# 06_LMS7002M_Power.net
KiCad netlist of a schematic drawn in Altium Designer
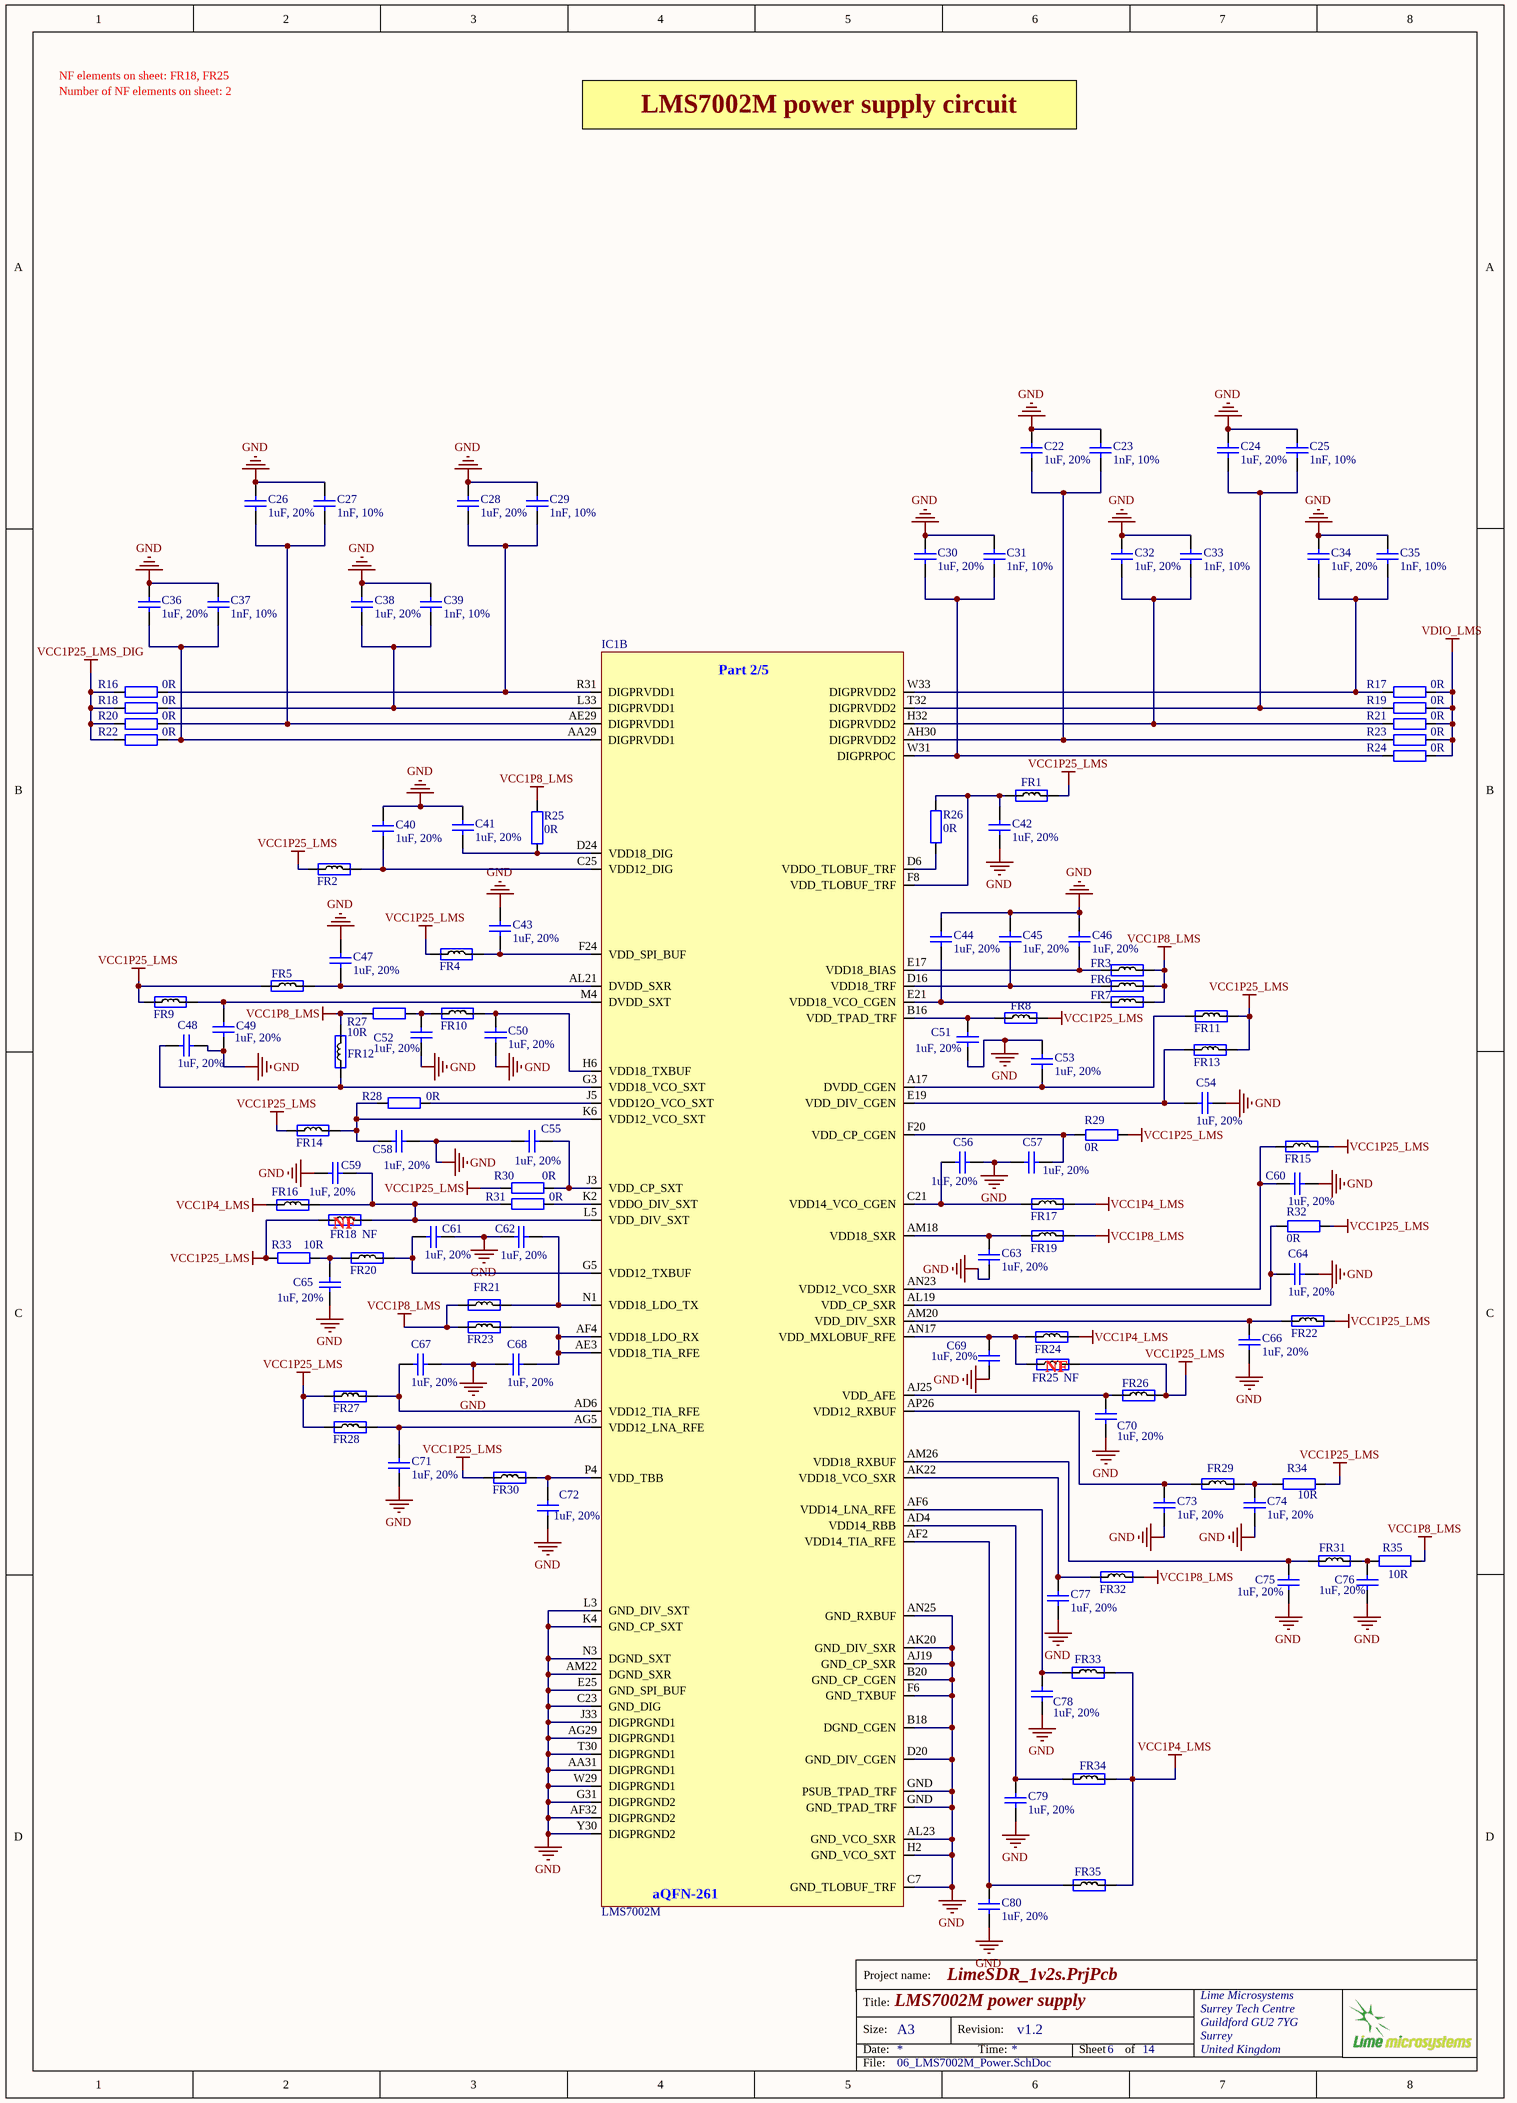
[diagram p0: 06_LMS7002M_Power.SchDoc]

(export (version "E")
  (design (tool "Eeschema 10.0.6"))
  (components
    (comp (ref "C22")
      (value "1uF, 20%")
      (footprint "CAP0201")
      (fields (field (name "TOLERANCE") "±20%") (field (name "MANUFACTURER") "TDK Corporation"))
      (libsource (lib "LimeMicroAltiumLib_schLib") (part "Cap_0402"))
    )
    (comp (ref "C23")
      (value "1nF, 10%")
      (footprint "CAP0201")
      (fields (field (name "TOLERANCE") "±10%") (field (name "MANUFACTURER") "TDK Corporation"))
      (libsource (lib "LimeMicroAltiumLib_schLib") (part "Cap_0402"))
    )
    (comp (ref "C24")
      (value "1uF, 20%")
      (footprint "CAP0201")
      (fields (field (name "TOLERANCE") "±20%") (field (name "MANUFACTURER") "TDK Corporation"))
      (libsource (lib "LimeMicroAltiumLib_schLib") (part "Cap_0402"))
    )
    (comp (ref "C25")
      (value "1nF, 10%")
      (footprint "CAP0201")
      (fields (field (name "TOLERANCE") "±10%") (field (name "MANUFACTURER") "TDK Corporation"))
      (libsource (lib "LimeMicroAltiumLib_schLib") (part "Cap_0402"))
    )
    (comp (ref "C26")
      (value "1uF, 20%")
      (footprint "CAP0201")
      (fields (field (name "TOLERANCE") "±20%") (field (name "MANUFACTURER") "TDK Corporation"))
      (libsource (lib "LimeMicroAltiumLib_schLib") (part "Cap_0402"))
    )
    (comp (ref "C27")
      (value "1nF, 10%")
      (footprint "CAP0201")
      (fields (field (name "TOLERANCE") "±10%") (field (name "MANUFACTURER") "TDK Corporation"))
      (libsource (lib "LimeMicroAltiumLib_schLib") (part "Cap_0402"))
    )
    (comp (ref "C28")
      (value "1uF, 20%")
      (footprint "CAP0201")
      (fields (field (name "TOLERANCE") "±20%") (field (name "MANUFACTURER") "TDK Corporation"))
      (libsource (lib "LimeMicroAltiumLib_schLib") (part "Cap_0402"))
    )
    (comp (ref "C29")
      (value "1nF, 10%")
      (footprint "CAP0201")
      (fields (field (name "TOLERANCE") "±10%") (field (name "MANUFACTURER") "TDK Corporation"))
      (libsource (lib "LimeMicroAltiumLib_schLib") (part "Cap_0402"))
    )
    (comp (ref "C30")
      (value "1uF, 20%")
      (footprint "CAP0201")
      (fields (field (name "TOLERANCE") "±20%") (field (name "MANUFACTURER") "TDK Corporation"))
      (libsource (lib "LimeMicroAltiumLib_schLib") (part "Cap_0402"))
    )
    (comp (ref "C31")
      (value "1nF, 10%")
      (footprint "CAP0201")
      (fields (field (name "TOLERANCE") "±10%") (field (name "MANUFACTURER") "TDK Corporation"))
      (libsource (lib "LimeMicroAltiumLib_schLib") (part "Cap_0402"))
    )
    (comp (ref "C32")
      (value "1uF, 20%")
      (footprint "CAP0201")
      (fields (field (name "TOLERANCE") "±20%") (field (name "MANUFACTURER") "TDK Corporation"))
      (libsource (lib "LimeMicroAltiumLib_schLib") (part "Cap_0402"))
    )
    (comp (ref "C33")
      (value "1nF, 10%")
      (footprint "CAP0201")
      (fields (field (name "TOLERANCE") "±10%") (field (name "MANUFACTURER") "TDK Corporation"))
      (libsource (lib "LimeMicroAltiumLib_schLib") (part "Cap_0402"))
    )
    (comp (ref "C34")
      (value "1uF, 20%")
      (footprint "CAP0201")
      (fields (field (name "TOLERANCE") "±20%") (field (name "MANUFACTURER") "TDK Corporation"))
      (libsource (lib "LimeMicroAltiumLib_schLib") (part "Cap_0402"))
    )
    (comp (ref "C35")
      (value "1nF, 10%")
      (footprint "CAP0201")
      (fields (field (name "TOLERANCE") "±10%") (field (name "MANUFACTURER") "TDK Corporation"))
      (libsource (lib "LimeMicroAltiumLib_schLib") (part "Cap_0402"))
    )
    (comp (ref "C36")
      (value "1uF, 20%")
      (footprint "CAP0201")
      (fields (field (name "TOLERANCE") "±20%") (field (name "MANUFACTURER") "TDK Corporation"))
      (libsource (lib "LimeMicroAltiumLib_schLib") (part "Cap_0402"))
    )
    (comp (ref "C37")
      (value "1nF, 10%")
      (footprint "CAP0201")
      (fields (field (name "TOLERANCE") "±10%") (field (name "MANUFACTURER") "TDK Corporation"))
      (libsource (lib "LimeMicroAltiumLib_schLib") (part "Cap_0402"))
    )
    (comp (ref "C38")
      (value "1uF, 20%")
      (footprint "CAP0201")
      (fields (field (name "TOLERANCE") "±20%") (field (name "MANUFACTURER") "TDK Corporation"))
      (libsource (lib "LimeMicroAltiumLib_schLib") (part "Cap_0402"))
    )
    (comp (ref "C39")
      (value "1nF, 10%")
      (footprint "CAP0201")
      (fields (field (name "TOLERANCE") "±10%") (field (name "MANUFACTURER") "TDK Corporation"))
      (libsource (lib "LimeMicroAltiumLib_schLib") (part "Cap_0402"))
    )
    (comp (ref "C40")
      (value "1uF, 20%")
      (footprint "CAP0201")
      (fields (field (name "TOLERANCE") "±20%") (field (name "MANUFACTURER") "TDK Corporation"))
      (libsource (lib "LimeMicroAltiumLib_schLib") (part "Cap_0402"))
    )
    (comp (ref "C41")
      (value "1uF, 20%")
      (footprint "CAP0201")
      (fields (field (name "TOLERANCE") "±20%") (field (name "MANUFACTURER") "TDK Corporation"))
      (libsource (lib "LimeMicroAltiumLib_schLib") (part "Cap_0402"))
    )
    (comp (ref "C42")
      (value "1uF, 20%")
      (footprint "CAP0201")
      (fields (field (name "TOLERANCE") "±20%") (field (name "MANUFACTURER") "TDK Corporation"))
      (libsource (lib "LimeMicroAltiumLib_schLib") (part "Cap_0402"))
    )
    (comp (ref "C43")
      (value "1uF, 20%")
      (footprint "CAP0201")
      (fields (field (name "TOLERANCE") "±20%") (field (name "MANUFACTURER") "TDK Corporation"))
      (libsource (lib "LimeMicroAltiumLib_schLib") (part "Cap_0402"))
    )
    (comp (ref "C44")
      (value "1uF, 20%")
      (footprint "CAP0201")
      (fields (field (name "TOLERANCE") "±20%") (field (name "MANUFACTURER") "TDK Corporation"))
      (libsource (lib "LimeMicroAltiumLib_schLib") (part "Cap_0402"))
    )
    (comp (ref "C45")
      (value "1uF, 20%")
      (footprint "CAP0201")
      (fields (field (name "TOLERANCE") "±20%") (field (name "MANUFACTURER") "TDK Corporation"))
      (libsource (lib "LimeMicroAltiumLib_schLib") (part "Cap_0402"))
    )
    (comp (ref "C46")
      (value "1uF, 20%")
      (footprint "CAP0201")
      (fields (field (name "TOLERANCE") "±20%") (field (name "MANUFACTURER") "TDK Corporation"))
      (libsource (lib "LimeMicroAltiumLib_schLib") (part "Cap_0402"))
    )
    (comp (ref "C47")
      (value "1uF, 20%")
      (footprint "CAP0201")
      (fields (field (name "TOLERANCE") "±20%") (field (name "MANUFACTURER") "TDK Corporation"))
      (libsource (lib "LimeMicroAltiumLib_schLib") (part "Cap_0402"))
    )
    (comp (ref "C48")
      (value "1uF, 20%")
      (footprint "CAP0201")
      (fields (field (name "TOLERANCE") "±20%") (field (name "MANUFACTURER") "TDK Corporation"))
      (libsource (lib "LimeMicroAltiumLib_schLib") (part "Cap_0402"))
    )
    (comp (ref "C49")
      (value "1uF, 20%")
      (footprint "CAP0201")
      (fields (field (name "TOLERANCE") "±20%") (field (name "MANUFACTURER") "TDK Corporation"))
      (libsource (lib "LimeMicroAltiumLib_schLib") (part "Cap_0402"))
    )
    (comp (ref "C50")
      (value "1uF, 20%")
      (footprint "CAP0201")
      (fields (field (name "TOLERANCE") "±20%") (field (name "MANUFACTURER") "TDK Corporation"))
      (libsource (lib "LimeMicroAltiumLib_schLib") (part "Cap_0402"))
    )
    (comp (ref "C51")
      (value "1uF, 20%")
      (footprint "CAP0201")
      (fields (field (name "TOLERANCE") "±20%") (field (name "MANUFACTURER") "TDK Corporation"))
      (libsource (lib "LimeMicroAltiumLib_schLib") (part "Cap_0402"))
    )
    (comp (ref "C52")
      (value "1uF, 20%")
      (footprint "CAP0201")
      (fields (field (name "TOLERANCE") "±20%") (field (name "MANUFACTURER") "TDK Corporation"))
      (libsource (lib "LimeMicroAltiumLib_schLib") (part "Cap_0402"))
    )
    (comp (ref "C53")
      (value "1uF, 20%")
      (footprint "CAP0201")
      (fields (field (name "TOLERANCE") "±20%") (field (name "MANUFACTURER") "TDK Corporation"))
      (libsource (lib "LimeMicroAltiumLib_schLib") (part "Cap_0402"))
    )
    (comp (ref "C54")
      (value "1uF, 20%")
      (footprint "CAP0201")
      (fields (field (name "TOLERANCE") "±20%") (field (name "MANUFACTURER") "TDK Corporation"))
      (libsource (lib "LimeMicroAltiumLib_schLib") (part "Cap_0402"))
    )
    (comp (ref "C55")
      (value "1uF, 20%")
      (footprint "CAP0201")
      (fields (field (name "TOLERANCE") "±20%") (field (name "MANUFACTURER") "TDK Corporation"))
      (libsource (lib "LimeMicroAltiumLib_schLib") (part "Cap_0402"))
    )
    (comp (ref "C56")
      (value "1uF, 20%")
      (footprint "CAP0201")
      (fields (field (name "TOLERANCE") "±20%") (field (name "MANUFACTURER") "TDK Corporation"))
      (libsource (lib "LimeMicroAltiumLib_schLib") (part "Cap_0402"))
    )
    (comp (ref "C57")
      (value "1uF, 20%")
      (footprint "CAP0201")
      (fields (field (name "TOLERANCE") "±20%") (field (name "MANUFACTURER") "TDK Corporation"))
      (libsource (lib "LimeMicroAltiumLib_schLib") (part "Cap_0402"))
    )
    (comp (ref "C58")
      (value "1uF, 20%")
      (footprint "CAP0201")
      (fields (field (name "TOLERANCE") "±20%") (field (name "MANUFACTURER") "TDK Corporation"))
      (libsource (lib "LimeMicroAltiumLib_schLib") (part "Cap_0402"))
    )
    (comp (ref "C59")
      (value "1uF, 20%")
      (footprint "CAP0201")
      (fields (field (name "TOLERANCE") "±20%") (field (name "MANUFACTURER") "TDK Corporation"))
      (libsource (lib "LimeMicroAltiumLib_schLib") (part "Cap_0402"))
    )
    (comp (ref "C60")
      (value "1uF, 20%")
      (footprint "CAP0201")
      (fields (field (name "TOLERANCE") "±20%") (field (name "MANUFACTURER") "TDK Corporation"))
      (libsource (lib "LimeMicroAltiumLib_schLib") (part "Cap_0402"))
    )
    (comp (ref "C61")
      (value "1uF, 20%")
      (footprint "CAP0201")
      (fields (field (name "TOLERANCE") "±20%") (field (name "MANUFACTURER") "TDK Corporation"))
      (libsource (lib "LimeMicroAltiumLib_schLib") (part "Cap_0402"))
    )
    (comp (ref "C62")
      (value "1uF, 20%")
      (footprint "CAP0201")
      (fields (field (name "TOLERANCE") "±20%") (field (name "MANUFACTURER") "TDK Corporation"))
      (libsource (lib "LimeMicroAltiumLib_schLib") (part "Cap_0402"))
    )
    (comp (ref "C63")
      (value "1uF, 20%")
      (footprint "CAP0201")
      (fields (field (name "TOLERANCE") "±20%") (field (name "MANUFACTURER") "TDK Corporation"))
      (libsource (lib "LimeMicroAltiumLib_schLib") (part "Cap_0402"))
    )
    (comp (ref "C64")
      (value "1uF, 20%")
      (footprint "CAP0201")
      (fields (field (name "TOLERANCE") "±20%") (field (name "MANUFACTURER") "TDK Corporation"))
      (libsource (lib "LimeMicroAltiumLib_schLib") (part "Cap_0402"))
    )
    (comp (ref "C65")
      (value "1uF, 20%")
      (footprint "CAP0201")
      (fields (field (name "TOLERANCE") "±20%") (field (name "MANUFACTURER") "TDK Corporation"))
      (libsource (lib "LimeMicroAltiumLib_schLib") (part "Cap_0402"))
    )
    (comp (ref "C66")
      (value "1uF, 20%")
      (footprint "CAP0201")
      (fields (field (name "TOLERANCE") "±20%") (field (name "MANUFACTURER") "TDK Corporation"))
      (libsource (lib "LimeMicroAltiumLib_schLib") (part "Cap_0402"))
    )
    (comp (ref "C67")
      (value "1uF, 20%")
      (footprint "CAP0201")
      (fields (field (name "TOLERANCE") "±20%") (field (name "MANUFACTURER") "TDK Corporation"))
      (libsource (lib "LimeMicroAltiumLib_schLib") (part "Cap_0402"))
    )
    (comp (ref "C68")
      (value "1uF, 20%")
      (footprint "CAP0201")
      (fields (field (name "TOLERANCE") "±20%") (field (name "MANUFACTURER") "TDK Corporation"))
      (libsource (lib "LimeMicroAltiumLib_schLib") (part "Cap_0402"))
    )
    (comp (ref "C69")
      (value "1uF, 20%")
      (footprint "CAP0201")
      (fields (field (name "TOLERANCE") "±20%") (field (name "MANUFACTURER") "TDK Corporation"))
      (libsource (lib "LimeMicroAltiumLib_schLib") (part "Cap_0402"))
    )
    (comp (ref "C70")
      (value "1uF, 20%")
      (footprint "CAP0201")
      (fields (field (name "TOLERANCE") "±20%") (field (name "MANUFACTURER") "TDK Corporation"))
      (libsource (lib "LimeMicroAltiumLib_schLib") (part "Cap_0402"))
    )
    (comp (ref "C71")
      (value "1uF, 20%")
      (footprint "CAP0201")
      (fields (field (name "TOLERANCE") "±20%") (field (name "MANUFACTURER") "TDK Corporation"))
      (libsource (lib "LimeMicroAltiumLib_schLib") (part "Cap_0402"))
    )
    (comp (ref "C72")
      (value "1uF, 20%")
      (footprint "CAP0201")
      (fields (field (name "TOLERANCE") "±20%") (field (name "MANUFACTURER") "TDK Corporation"))
      (libsource (lib "LimeMicroAltiumLib_schLib") (part "Cap_0402"))
    )
    (comp (ref "C73")
      (value "1uF, 20%")
      (footprint "CAP0201")
      (fields (field (name "TOLERANCE") "±20%") (field (name "MANUFACTURER") "TDK Corporation"))
      (libsource (lib "LimeMicroAltiumLib_schLib") (part "Cap_0402"))
    )
    (comp (ref "C74")
      (value "1uF, 20%")
      (footprint "CAP0201")
      (fields (field (name "TOLERANCE") "±20%") (field (name "MANUFACTURER") "TDK Corporation"))
      (libsource (lib "LimeMicroAltiumLib_schLib") (part "Cap_0402"))
    )
    (comp (ref "C75")
      (value "1uF, 20%")
      (footprint "CAP0201")
      (fields (field (name "TOLERANCE") "±20%") (field (name "MANUFACTURER") "TDK Corporation"))
      (libsource (lib "LimeMicroAltiumLib_schLib") (part "Cap_0402"))
    )
    (comp (ref "C76")
      (value "1uF, 20%")
      (footprint "CAP0201")
      (fields (field (name "TOLERANCE") "±20%") (field (name "MANUFACTURER") "TDK Corporation"))
      (libsource (lib "LimeMicroAltiumLib_schLib") (part "Cap_0402"))
    )
    (comp (ref "C77")
      (value "1uF, 20%")
      (footprint "CAP0201")
      (fields (field (name "TOLERANCE") "±20%") (field (name "MANUFACTURER") "TDK Corporation"))
      (libsource (lib "LimeMicroAltiumLib_schLib") (part "Cap_0402"))
    )
    (comp (ref "C78")
      (value "1uF, 20%")
      (footprint "CAP0201")
      (fields (field (name "TOLERANCE") "±20%") (field (name "MANUFACTURER") "TDK Corporation"))
      (libsource (lib "LimeMicroAltiumLib_schLib") (part "Cap_0402"))
    )
    (comp (ref "C79")
      (value "1uF, 20%")
      (footprint "CAP0201")
      (fields (field (name "TOLERANCE") "±20%") (field (name "MANUFACTURER") "TDK Corporation"))
      (libsource (lib "LimeMicroAltiumLib_schLib") (part "Cap_0402"))
    )
    (comp (ref "C80")
      (value "1uF, 20%")
      (footprint "CAP0201")
      (fields (field (name "TOLERANCE") "±20%") (field (name "MANUFACTURER") "TDK Corporation"))
      (libsource (lib "LimeMicroAltiumLib_schLib") (part "Cap_0402"))
    )
    (comp (ref "FR1")
      (value "Ferrite")
      (footprint "RES0201")
      (fields (field (name "MANUFACTURER") "Taiyo Yuden"))
      (libsource (lib "LimeMicroAltiumLib_schLib") (part "Ferrite"))
    )
    (comp (ref "FR2")
      (value "Ferrite")
      (footprint "RES0201")
      (fields (field (name "MANUFACTURER") "Taiyo Yuden"))
      (libsource (lib "LimeMicroAltiumLib_schLib") (part "Ferrite"))
    )
    (comp (ref "FR3")
      (value "Ferrite")
      (footprint "RES0201")
      (fields (field (name "MANUFACTURER") "Taiyo Yuden"))
      (libsource (lib "LimeMicroAltiumLib_schLib") (part "Ferrite"))
    )
    (comp (ref "FR4")
      (value "Ferrite")
      (footprint "RES0201")
      (fields (field (name "MANUFACTURER") "Taiyo Yuden"))
      (libsource (lib "LimeMicroAltiumLib_schLib") (part "Ferrite"))
    )
    (comp (ref "FR5")
      (value "Ferrite")
      (footprint "RES0201")
      (fields (field (name "MANUFACTURER") "Taiyo Yuden"))
      (libsource (lib "LimeMicroAltiumLib_schLib") (part "Ferrite"))
    )
    (comp (ref "FR6")
      (value "Ferrite")
      (footprint "RES0201")
      (fields (field (name "MANUFACTURER") "Taiyo Yuden"))
      (libsource (lib "LimeMicroAltiumLib_schLib") (part "Ferrite"))
    )
    (comp (ref "FR7")
      (value "Ferrite")
      (footprint "RES0201")
      (fields (field (name "MANUFACTURER") "Taiyo Yuden"))
      (libsource (lib "LimeMicroAltiumLib_schLib") (part "Ferrite"))
    )
    (comp (ref "FR8")
      (value "Ferrite")
      (footprint "RES0201")
      (fields (field (name "MANUFACTURER") "Taiyo Yuden"))
      (libsource (lib "LimeMicroAltiumLib_schLib") (part "Ferrite"))
    )
    (comp (ref "FR9")
      (value "Ferrite")
      (footprint "RES0201")
      (fields (field (name "MANUFACTURER") "Taiyo Yuden"))
      (libsource (lib "LimeMicroAltiumLib_schLib") (part "Ferrite"))
    )
    (comp (ref "FR10")
      (value "Ferrite")
      (footprint "RES0201")
      (fields (field (name "MANUFACTURER") "Taiyo Yuden"))
      (libsource (lib "LimeMicroAltiumLib_schLib") (part "Ferrite"))
    )
    (comp (ref "FR11")
      (value "Ferrite")
      (footprint "RES0201")
      (fields (field (name "MANUFACTURER") "Taiyo Yuden"))
      (libsource (lib "LimeMicroAltiumLib_schLib") (part "Ferrite"))
    )
    (comp (ref "FR12")
      (value "Ferrite")
      (footprint "RES0201")
      (fields (field (name "MANUFACTURER") "Taiyo Yuden"))
      (libsource (lib "LimeMicroAltiumLib_schLib") (part "Ferrite"))
    )
    (comp (ref "FR13")
      (value "Ferrite")
      (footprint "RES0201")
      (fields (field (name "MANUFACTURER") "Taiyo Yuden"))
      (libsource (lib "LimeMicroAltiumLib_schLib") (part "Ferrite"))
    )
    (comp (ref "FR14")
      (value "Ferrite")
      (footprint "RES0201")
      (fields (field (name "MANUFACTURER") "Taiyo Yuden"))
      (libsource (lib "LimeMicroAltiumLib_schLib") (part "Ferrite"))
    )
    (comp (ref "FR15")
      (value "Ferrite")
      (footprint "RES0201")
      (fields (field (name "MANUFACTURER") "Taiyo Yuden"))
      (libsource (lib "LimeMicroAltiumLib_schLib") (part "Ferrite"))
    )
    (comp (ref "FR16")
      (value "Ferrite")
      (footprint "RES0201")
      (fields (field (name "MANUFACTURER") "Taiyo Yuden"))
      (libsource (lib "LimeMicroAltiumLib_schLib") (part "Ferrite"))
    )
    (comp (ref "FR17")
      (value "Ferrite")
      (footprint "RES0201")
      (fields (field (name "MANUFACTURER") "Taiyo Yuden"))
      (libsource (lib "LimeMicroAltiumLib_schLib") (part "Ferrite"))
    )
    (comp (ref "FR18")
      (value "Ferrite")
      (footprint "RES0201")
      (fields (field (name "MANUFACTURER") "Taiyo Yuden") (field (name "ASSEMBLY INFO") "NF"))
      (libsource (lib "LimeMicroAltiumLib_schLib") (part "Ferrite"))
    )
    (comp (ref "FR19")
      (value "Ferrite")
      (footprint "RES0201")
      (fields (field (name "MANUFACTURER") "Taiyo Yuden"))
      (libsource (lib "LimeMicroAltiumLib_schLib") (part "Ferrite"))
    )
    (comp (ref "FR20")
      (value "Ferrite")
      (footprint "RES0201")
      (fields (field (name "MANUFACTURER") "Taiyo Yuden"))
      (libsource (lib "LimeMicroAltiumLib_schLib") (part "Ferrite"))
    )
    (comp (ref "FR21")
      (value "Ferrite")
      (footprint "RES0201")
      (fields (field (name "MANUFACTURER") "Taiyo Yuden"))
      (libsource (lib "LimeMicroAltiumLib_schLib") (part "Ferrite"))
    )
    (comp (ref "FR22")
      (value "Ferrite")
      (footprint "RES0201")
      (fields (field (name "MANUFACTURER") "Taiyo Yuden"))
      (libsource (lib "LimeMicroAltiumLib_schLib") (part "Ferrite"))
    )
    (comp (ref "FR23")
      (value "Ferrite")
      (footprint "RES0201")
      (fields (field (name "MANUFACTURER") "Taiyo Yuden"))
      (libsource (lib "LimeMicroAltiumLib_schLib") (part "Ferrite"))
    )
    (comp (ref "FR24")
      (value "Ferrite")
      (footprint "RES0201")
      (fields (field (name "MANUFACTURER") "Taiyo Yuden"))
      (libsource (lib "LimeMicroAltiumLib_schLib") (part "Ferrite"))
    )
    (comp (ref "FR25")
      (value "Ferrite")
      (footprint "RES0201")
      (fields (field (name "MANUFACTURER") "Taiyo Yuden") (field (name "ASSEMBLY INFO") "NF"))
      (libsource (lib "LimeMicroAltiumLib_schLib") (part "Ferrite"))
    )
    (comp (ref "FR26")
      (value "Ferrite")
      (footprint "RES0201")
      (fields (field (name "MANUFACTURER") "Taiyo Yuden"))
      (libsource (lib "LimeMicroAltiumLib_schLib") (part "Ferrite"))
    )
    (comp (ref "FR27")
      (value "Ferrite")
      (footprint "RES0201")
      (fields (field (name "MANUFACTURER") "Taiyo Yuden"))
      (libsource (lib "LimeMicroAltiumLib_schLib") (part "Ferrite"))
    )
    (comp (ref "FR28")
      (value "Ferrite")
      (footprint "RES0201")
      (fields (field (name "MANUFACTURER") "Taiyo Yuden"))
      (libsource (lib "LimeMicroAltiumLib_schLib") (part "Ferrite"))
    )
    (comp (ref "FR29")
      (value "Ferrite")
      (footprint "RES0201")
      (fields (field (name "MANUFACTURER") "Taiyo Yuden"))
      (libsource (lib "LimeMicroAltiumLib_schLib") (part "Ferrite"))
    )
    (comp (ref "FR30")
      (value "Ferrite")
      (footprint "RES0201")
      (fields (field (name "MANUFACTURER") "Taiyo Yuden"))
      (libsource (lib "LimeMicroAltiumLib_schLib") (part "Ferrite"))
    )
    (comp (ref "FR31")
      (value "Ferrite")
      (footprint "RES0201")
      (fields (field (name "MANUFACTURER") "Taiyo Yuden"))
      (libsource (lib "LimeMicroAltiumLib_schLib") (part "Ferrite"))
    )
    (comp (ref "FR32")
      (value "Ferrite")
      (footprint "RES0201")
      (fields (field (name "MANUFACTURER") "Taiyo Yuden"))
      (libsource (lib "LimeMicroAltiumLib_schLib") (part "Ferrite"))
    )
    (comp (ref "FR33")
      (value "Ferrite")
      (footprint "RES0201")
      (fields (field (name "MANUFACTURER") "Taiyo Yuden"))
      (libsource (lib "LimeMicroAltiumLib_schLib") (part "Ferrite"))
    )
    (comp (ref "FR34")
      (value "Ferrite")
      (footprint "RES0201")
      (fields (field (name "MANUFACTURER") "Taiyo Yuden"))
      (libsource (lib "LimeMicroAltiumLib_schLib") (part "Ferrite"))
    )
    (comp (ref "FR35")
      (value "Ferrite")
      (footprint "RES0201")
      (fields (field (name "MANUFACTURER") "Taiyo Yuden"))
      (libsource (lib "LimeMicroAltiumLib_schLib") (part "Ferrite"))
    )
    (comp (ref "IC1")
      (value "LMS7002M")
      (footprint "LMS7002M")
      (fields (field (name "MANUFACTURER") "Lime Microsystems"))
      (libsource (lib "LimeMicroAltiumLib_schLib") (part "LMS7002M"))
    )
    (comp (ref "R16")
      (value "0R")
      (footprint "RES0402")
      (fields (field (name "MANUFACTURER") "Yageo") (field (name "TOLERANCE") "Jumper"))
      (libsource (lib "LimeMicroAltiumLib_schLib") (part "Res_0402"))
    )
    (comp (ref "R17")
      (value "0R")
      (footprint "RES0402")
      (fields (field (name "MANUFACTURER") "Yageo") (field (name "TOLERANCE") "Jumper"))
      (libsource (lib "LimeMicroAltiumLib_schLib") (part "Res_0402"))
    )
    (comp (ref "R18")
      (value "0R")
      (footprint "RES0402")
      (fields (field (name "MANUFACTURER") "Yageo") (field (name "TOLERANCE") "Jumper"))
      (libsource (lib "LimeMicroAltiumLib_schLib") (part "Res_0402"))
    )
    (comp (ref "R19")
      (value "0R")
      (footprint "RES0402")
      (fields (field (name "MANUFACTURER") "Yageo") (field (name "TOLERANCE") "Jumper"))
      (libsource (lib "LimeMicroAltiumLib_schLib") (part "Res_0402"))
    )
    (comp (ref "R20")
      (value "0R")
      (footprint "RES0402")
      (fields (field (name "MANUFACTURER") "Yageo") (field (name "TOLERANCE") "Jumper"))
      (libsource (lib "LimeMicroAltiumLib_schLib") (part "Res_0402"))
    )
    (comp (ref "R21")
      (value "0R")
      (footprint "RES0402")
      (fields (field (name "MANUFACTURER") "Yageo") (field (name "TOLERANCE") "Jumper"))
      (libsource (lib "LimeMicroAltiumLib_schLib") (part "Res_0402"))
    )
    (comp (ref "R22")
      (value "0R")
      (footprint "RES0402")
      (fields (field (name "MANUFACTURER") "Yageo") (field (name "TOLERANCE") "Jumper"))
      (libsource (lib "LimeMicroAltiumLib_schLib") (part "Res_0402"))
    )
    (comp (ref "R23")
      (value "0R")
      (footprint "RES0402")
      (fields (field (name "MANUFACTURER") "Yageo") (field (name "TOLERANCE") "Jumper"))
      (libsource (lib "LimeMicroAltiumLib_schLib") (part "Res_0402"))
    )
    (comp (ref "R24")
      (value "0R")
      (footprint "RES0402")
      (fields (field (name "MANUFACTURER") "Yageo") (field (name "TOLERANCE") "Jumper"))
      (libsource (lib "LimeMicroAltiumLib_schLib") (part "Res_0402"))
    )
    (comp (ref "R25")
      (value "0R")
      (footprint "RES0201")
      (fields (field (name "MANUFACTURER") "Rohm Semiconductor") (field (name "TOLERANCE") "Jumper"))
      (libsource (lib "LimeMicroAltiumLib_schLib") (part "Res_0402"))
    )
    (comp (ref "R26")
      (value "0R")
      (footprint "RES0201")
      (fields (field (name "MANUFACTURER") "Rohm Semiconductor") (field (name "TOLERANCE") "Jumper"))
      (libsource (lib "LimeMicroAltiumLib_schLib") (part "Res_0402"))
    )
    (comp (ref "R27")
      (value "10R")
      (footprint "RES0201")
      (fields
        (field (name "MANUFACTURER") "Panasonic Electronic Components")
        (field (name "TOLERANCE") "±1%")
        (field (name "MANUFACTURER PART NUMBER") "ERJ-1GEF10R0C")
      )
      (libsource (lib "LimeMicroAltiumLib_schLib") (part "Res_0402"))
    )
    (comp (ref "R28")
      (value "0R")
      (footprint "RES0201")
      (fields (field (name "MANUFACTURER") "Rohm Semiconductor") (field (name "TOLERANCE") "Jumper"))
      (libsource (lib "LimeMicroAltiumLib_schLib") (part "Res_0402"))
    )
    (comp (ref "R29")
      (value "0R")
      (footprint "RES0201")
      (fields (field (name "MANUFACTURER") "Rohm Semiconductor") (field (name "TOLERANCE") "Jumper"))
      (libsource (lib "LimeMicroAltiumLib_schLib") (part "Res_0402"))
    )
    (comp (ref "R30")
      (value "0R")
      (footprint "RES0201")
      (fields (field (name "MANUFACTURER") "Rohm Semiconductor") (field (name "TOLERANCE") "Jumper"))
      (libsource (lib "LimeMicroAltiumLib_schLib") (part "Res_0402"))
    )
    (comp (ref "R31")
      (value "0R")
      (footprint "RES0201")
      (fields (field (name "MANUFACTURER") "Rohm Semiconductor") (field (name "TOLERANCE") "Jumper"))
      (libsource (lib "LimeMicroAltiumLib_schLib") (part "Res_0402"))
    )
    (comp (ref "R32")
      (value "0R")
      (footprint "RES0201")
      (fields (field (name "MANUFACTURER") "Rohm Semiconductor") (field (name "TOLERANCE") "Jumper"))
      (libsource (lib "LimeMicroAltiumLib_schLib") (part "Res_0402"))
    )
    (comp (ref "R33")
      (value "10R")
      (footprint "RES0201")
      (fields
        (field (name "MANUFACTURER") "Panasonic Electronic Components")
        (field (name "TOLERANCE") "±1%")
        (field (name "MANUFACTURER PART NUMBER") "ERJ-1GEF10R0C")
      )
      (libsource (lib "LimeMicroAltiumLib_schLib") (part "Res_0402"))
    )
    (comp (ref "R34")
      (value "10R")
      (footprint "RES0201")
      (fields
        (field (name "MANUFACTURER") "Panasonic Electronic Components")
        (field (name "TOLERANCE") "±1%")
        (field (name "MANUFACTURER PART NUMBER") "ERJ-1GEF10R0C")
      )
      (libsource (lib "LimeMicroAltiumLib_schLib") (part "Res_0402"))
    )
    (comp (ref "R35")
      (value "10R")
      (footprint "RES0201")
      (fields
        (field (name "MANUFACTURER") "Panasonic Electronic Components")
        (field (name "TOLERANCE") "±1%")
        (field (name "MANUFACTURER PART NUMBER") "ERJ-1GEF10R0C")
      )
      (libsource (lib "LimeMicroAltiumLib_schLib") (part "Res_0402"))
    )
  )
  (nets
    (net (code "1") (name "GND") (class "Default")
      (node (ref "C22") (pin "2") (pinfunction "2_2") (pintype "passive"))
      (node (ref "C23") (pin "2") (pinfunction "2_2") (pintype "passive"))
      (node (ref "C24") (pin "2") (pinfunction "2_2") (pintype "passive"))
      (node (ref "C25") (pin "2") (pinfunction "2_2") (pintype "passive"))
      (node (ref "C26") (pin "2") (pinfunction "2_2") (pintype "passive"))
      (node (ref "C27") (pin "2") (pinfunction "2_2") (pintype "passive"))
      (node (ref "C28") (pin "2") (pinfunction "2_2") (pintype "passive"))
      (node (ref "C29") (pin "2") (pinfunction "2_2") (pintype "passive"))
      (node (ref "C30") (pin "2") (pinfunction "2_2") (pintype "passive"))
      (node (ref "C31") (pin "2") (pinfunction "2_2") (pintype "passive"))
      (node (ref "C32") (pin "2") (pinfunction "2_2") (pintype "passive"))
      (node (ref "C33") (pin "2") (pinfunction "2_2") (pintype "passive"))
      (node (ref "C34") (pin "2") (pinfunction "2_2") (pintype "passive"))
      (node (ref "C35") (pin "2") (pinfunction "2_2") (pintype "passive"))
      (node (ref "C36") (pin "2") (pinfunction "2_2") (pintype "passive"))
      (node (ref "C37") (pin "2") (pinfunction "2_2") (pintype "passive"))
      (node (ref "C38") (pin "2") (pinfunction "2_2") (pintype "passive"))
      (node (ref "C39") (pin "2") (pinfunction "2_2") (pintype "passive"))
      (node (ref "C40") (pin "2") (pinfunction "2_2") (pintype "passive"))
      (node (ref "C41") (pin "2") (pinfunction "2_2") (pintype "passive"))
      (node (ref "C42") (pin "2") (pinfunction "2_2") (pintype "passive"))
      (node (ref "C43") (pin "2") (pinfunction "2_2") (pintype "passive"))
      (node (ref "C44") (pin "2") (pinfunction "2_2") (pintype "passive"))
      (node (ref "C45") (pin "2") (pinfunction "2_2") (pintype "passive"))
      (node (ref "C46") (pin "2") (pinfunction "2_2") (pintype "passive"))
      (node (ref "C47") (pin "2") (pinfunction "2_2") (pintype "passive"))
      (node (ref "C48") (pin "2") (pinfunction "2_2") (pintype "passive"))
      (node (ref "C49") (pin "2") (pinfunction "2_2") (pintype "passive"))
      (node (ref "C50") (pin "2") (pinfunction "2_2") (pintype "passive"))
      (node (ref "C51") (pin "2") (pinfunction "2_2") (pintype "passive"))
      (node (ref "C52") (pin "2") (pinfunction "2_2") (pintype "passive"))
      (node (ref "C53") (pin "2") (pinfunction "2_2") (pintype "passive"))
      (node (ref "C54") (pin "2") (pinfunction "2_2") (pintype "passive"))
      (node (ref "C55") (pin "2") (pinfunction "2_2") (pintype "passive"))
      (node (ref "C56") (pin "2") (pinfunction "2_2") (pintype "passive"))
      (node (ref "C57") (pin "2") (pinfunction "2_2") (pintype "passive"))
      (node (ref "C58") (pin "1") (pinfunction "1_1") (pintype "passive"))
      (node (ref "C59") (pin "2") (pinfunction "2_2") (pintype "passive"))
      (node (ref "C60") (pin "2") (pinfunction "2_2") (pintype "passive"))
      (node (ref "C61") (pin "2") (pinfunction "2_2") (pintype "passive"))
      (node (ref "C62") (pin "2") (pinfunction "2_2") (pintype "passive"))
      (node (ref "C63") (pin "2") (pinfunction "2_2") (pintype "passive"))
      (node (ref "C64") (pin "2") (pinfunction "2_2") (pintype "passive"))
      (node (ref "C65") (pin "2") (pinfunction "2_2") (pintype "passive"))
      (node (ref "C66") (pin "2") (pinfunction "2_2") (pintype "passive"))
      (node (ref "C67") (pin "2") (pinfunction "2_2") (pintype "passive"))
      (node (ref "C68") (pin "2") (pinfunction "2_2") (pintype "passive"))
      (node (ref "C69") (pin "2") (pinfunction "2_2") (pintype "passive"))
      (node (ref "C70") (pin "2") (pinfunction "2_2") (pintype "passive"))
      (node (ref "C71") (pin "2") (pinfunction "2_2") (pintype "passive"))
      (node (ref "C72") (pin "2") (pinfunction "2_2") (pintype "passive"))
      (node (ref "C73") (pin "2") (pinfunction "2_2") (pintype "passive"))
      (node (ref "C74") (pin "2") (pinfunction "2_2") (pintype "passive"))
      (node (ref "C75") (pin "2") (pinfunction "2_2") (pintype "passive"))
      (node (ref "C76") (pin "2") (pinfunction "2_2") (pintype "passive"))
      (node (ref "C77") (pin "2") (pinfunction "2_2") (pintype "passive"))
      (node (ref "C78") (pin "2") (pinfunction "2_2") (pintype "passive"))
      (node (ref "C79") (pin "2") (pinfunction "2_2") (pintype "passive"))
      (node (ref "C80") (pin "2") (pinfunction "2_2") (pintype "passive"))
      (node (ref "IC1") (pin "AA31") (pinfunction "DIGPRGND1_AA31") (pintype "passive"))
      (node (ref "IC1") (pin "AF32") (pinfunction "DIGPRGND2_AF32") (pintype "passive"))
      (node (ref "IC1") (pin "AG29") (pinfunction "DIGPRGND1_AG29") (pintype "passive"))
      (node (ref "IC1") (pin "AJ19") (pinfunction "GND_CP_SXR_AJ19") (pintype "passive"))
      (node (ref "IC1") (pin "AK20") (pinfunction "GND_DIV_SXR_AK20") (pintype "passive"))
      (node (ref "IC1") (pin "AL23") (pinfunction "GND_VCO_SXR_AL23") (pintype "passive"))
      (node (ref "IC1") (pin "AM22") (pinfunction "DGND_SXR_AM22") (pintype "passive"))
      (node (ref "IC1") (pin "AN25") (pinfunction "GND_RXBUF_AN25") (pintype "passive"))
      (node (ref "IC1") (pin "B18") (pinfunction "DGND_CGEN_B18") (pintype "passive"))
      (node (ref "IC1") (pin "B20") (pinfunction "GND_CP_CGEN_B20") (pintype "passive"))
      (node (ref "IC1") (pin "C23") (pinfunction "GND_DIG_C23") (pintype "passive"))
      (node (ref "IC1") (pin "C7") (pinfunction "GND_TLOBUF_TRF_C7") (pintype "passive"))
      (node (ref "IC1") (pin "D20") (pinfunction "GND_DIV_CGEN_D20") (pintype "passive"))
      (node (ref "IC1") (pin "E25") (pinfunction "GND_SPI_BUF_E25") (pintype "passive"))
      (node (ref "IC1") (pin "F6") (pinfunction "GND_TXBUF_F6") (pintype "passive"))
      (node (ref "IC1") (pin "G31") (pinfunction "DIGPRGND2_G31") (pintype "passive"))
      (node (ref "IC1") (pin "GND") (pinfunction "GND_TPAD_TRF_GND") (pintype "passive"))
      (node (ref "IC1") (pin "H2") (pinfunction "GND_VCO_SXT_H2") (pintype "passive"))
      (node (ref "IC1") (pin "J33") (pinfunction "DIGPRGND1_J33") (pintype "passive"))
      (node (ref "IC1") (pin "K4") (pinfunction "GND_CP_SXT_K4") (pintype "passive"))
      (node (ref "IC1") (pin "L3") (pinfunction "GND_DIV_SXT_L3") (pintype "passive"))
      (node (ref "IC1") (pin "N3") (pinfunction "DGND_SXT_N3") (pintype "passive"))
      (node (ref "IC1") (pin "T30") (pinfunction "DIGPRGND1_T30") (pintype "passive"))
      (node (ref "IC1") (pin "W29") (pinfunction "DIGPRGND1_W29") (pintype "passive"))
      (node (ref "IC1") (pin "Y30") (pinfunction "DIGPRGND2_Y30") (pintype "passive"))
    )
    (net (code "2") (name "Net-(C22-Pad1)") (class "Default")
      (node (ref "C22") (pin "1") (pinfunction "1_1") (pintype "passive"))
      (node (ref "C23") (pin "1") (pinfunction "1_1") (pintype "passive"))
      (node (ref "IC1") (pin "AH30") (pinfunction "DIGPRVDD2_AH30") (pintype "passive"))
      (node (ref "R23") (pin "2") (pinfunction "2_2") (pintype "passive"))
    )
    (net (code "3") (name "Net-(C24-Pad1)") (class "Default")
      (node (ref "C24") (pin "1") (pinfunction "1_1") (pintype "passive"))
      (node (ref "C25") (pin "1") (pinfunction "1_1") (pintype "passive"))
      (node (ref "IC1") (pin "T32") (pinfunction "DIGPRVDD2_T32") (pintype "passive"))
      (node (ref "R19") (pin "2") (pinfunction "2_2") (pintype "passive"))
    )
    (net (code "4") (name "Net-(C26-Pad1)") (class "Default")
      (node (ref "C26") (pin "1") (pinfunction "1_1") (pintype "passive"))
      (node (ref "C27") (pin "1") (pinfunction "1_1") (pintype "passive"))
      (node (ref "IC1") (pin "AE29") (pinfunction "DIGPRVDD1_AE29") (pintype "passive"))
      (node (ref "R20") (pin "1") (pinfunction "1_1") (pintype "passive"))
    )
    (net (code "5") (name "Net-(C28-Pad1)") (class "Default")
      (node (ref "C28") (pin "1") (pinfunction "1_1") (pintype "passive"))
      (node (ref "C29") (pin "1") (pinfunction "1_1") (pintype "passive"))
      (node (ref "IC1") (pin "R31") (pinfunction "DIGPRVDD1_R31") (pintype "passive"))
      (node (ref "R16") (pin "1") (pinfunction "1_1") (pintype "passive"))
    )
    (net (code "6") (name "Net-(C32-Pad1)") (class "Default")
      (node (ref "C32") (pin "1") (pinfunction "1_1") (pintype "passive"))
      (node (ref "C33") (pin "1") (pinfunction "1_1") (pintype "passive"))
      (node (ref "IC1") (pin "H32") (pinfunction "DIGPRVDD2_H32") (pintype "passive"))
      (node (ref "R21") (pin "2") (pinfunction "2_2") (pintype "passive"))
    )
    (net (code "7") (name "Net-(C34-Pad1)") (class "Default")
      (node (ref "C34") (pin "1") (pinfunction "1_1") (pintype "passive"))
      (node (ref "C35") (pin "1") (pinfunction "1_1") (pintype "passive"))
      (node (ref "IC1") (pin "W33") (pinfunction "DIGPRVDD2_W33") (pintype "passive"))
      (node (ref "R17") (pin "2") (pinfunction "2_2") (pintype "passive"))
    )
    (net (code "8") (name "Net-(C36-Pad1)") (class "Default")
      (node (ref "C36") (pin "1") (pinfunction "1_1") (pintype "passive"))
      (node (ref "C37") (pin "1") (pinfunction "1_1") (pintype "passive"))
      (node (ref "IC1") (pin "AA29") (pinfunction "DIGPRVDD1_AA29") (pintype "passive"))
      (node (ref "R22") (pin "1") (pinfunction "1_1") (pintype "passive"))
    )
    (net (code "9") (name "Net-(C38-Pad1)") (class "Default")
      (node (ref "C38") (pin "1") (pinfunction "1_1") (pintype "passive"))
      (node (ref "C39") (pin "1") (pinfunction "1_1") (pintype "passive"))
      (node (ref "IC1") (pin "L33") (pinfunction "DIGPRVDD1_L33") (pintype "passive"))
      (node (ref "R18") (pin "1") (pinfunction "1_1") (pintype "passive"))
    )
    (net (code "10") (name "Net-(C52-Pad1)") (class "Default")
      (node (ref "C52") (pin "1") (pinfunction "1_1") (pintype "passive"))
      (node (ref "FR10") (pin "1") (pinfunction "1_1") (pintype "passive"))
      (node (ref "R27") (pin "1") (pinfunction "1_1") (pintype "passive"))
    )
    (net (code "11") (name "Net-(C65-Pad1)") (class "Default")
      (node (ref "C65") (pin "1") (pinfunction "1_1") (pintype "passive"))
      (node (ref "FR20") (pin "1") (pinfunction "1_1") (pintype "passive"))
      (node (ref "R33") (pin "1") (pinfunction "1_1") (pintype "passive"))
    )
    (net (code "12") (name "Net-(C74-Pad1)") (class "Default")
      (node (ref "C74") (pin "1") (pinfunction "1_1") (pintype "passive"))
      (node (ref "FR29") (pin "2") (pinfunction "2_2") (pintype "passive"))
      (node (ref "R34") (pin "2") (pinfunction "2_2") (pintype "passive"))
    )
    (net (code "13") (name "Net-(C76-Pad1)") (class "Default")
      (node (ref "C76") (pin "1") (pinfunction "1_1") (pintype "passive"))
      (node (ref "FR31") (pin "2") (pinfunction "2_2") (pintype "passive"))
      (node (ref "R35") (pin "2") (pinfunction "2_2") (pintype "passive"))
    )
    (net (code "14") (name "Net-(IC1B-DIGPRPOC)") (class "Default")
      (node (ref "C30") (pin "1") (pinfunction "1_1") (pintype "passive"))
      (node (ref "C31") (pin "1") (pinfunction "1_1") (pintype "passive"))
      (node (ref "IC1") (pin "W31") (pinfunction "DIGPRPOC_W31") (pintype "passive"))
      (node (ref "R24") (pin "2") (pinfunction "2_2") (pintype "passive"))
    )
    (net (code "15") (name "Net-(IC1B-DVDD_CGEN)") (class "Default")
      (node (ref "C53") (pin "1") (pinfunction "1_1") (pintype "passive"))
      (node (ref "FR11") (pin "1") (pinfunction "1_1") (pintype "passive"))
      (node (ref "IC1") (pin "A17") (pinfunction "DVDD_CGEN_A17") (pintype "passive"))
    )
    (net (code "16") (name "Net-(IC1B-DVDD_SXR)") (class "Default")
      (node (ref "C47") (pin "1") (pinfunction "1_1") (pintype "passive"))
      (node (ref "FR5") (pin "2") (pinfunction "2_2") (pintype "passive"))
      (node (ref "IC1") (pin "AL21") (pinfunction "DVDD_SXR_AL21") (pintype "passive"))
    )
    (net (code "17") (name "Net-(IC1B-DVDD_SXT)") (class "Default")
      (node (ref "C49") (pin "1") (pinfunction "1_1") (pintype "passive"))
      (node (ref "FR9") (pin "2") (pinfunction "2_2") (pintype "passive"))
      (node (ref "IC1") (pin "M4") (pinfunction "DVDD_SXT_M4") (pintype "passive"))
    )
    (net (code "18") (name "Net-(IC1B-VDD12O_VCO_SXT)") (class "Default")
      (node (ref "IC1") (pin "J5") (pinfunction "VDD12O_VCO_SXT_J5") (pintype "passive"))
      (node (ref "R28") (pin "1") (pinfunction "1_1") (pintype "passive"))
    )
    (net (code "19") (name "Net-(IC1B-VDD12_DIG)") (class "Default")
      (node (ref "C40") (pin "1") (pinfunction "1_1") (pintype "passive"))
      (node (ref "FR2") (pin "2") (pinfunction "2_2") (pintype "passive"))
      (node (ref "IC1") (pin "C25") (pinfunction "VDD12_DIG_C25") (pintype "passive"))
    )
    (net (code "20") (name "Net-(IC1B-VDD12_LNA_RFE)") (class "Default")
      (node (ref "C71") (pin "1") (pinfunction "1_1") (pintype "passive"))
      (node (ref "FR28") (pin "2") (pinfunction "2_2") (pintype "passive"))
      (node (ref "IC1") (pin "AG5") (pinfunction "VDD12_LNA_RFE_AG5") (pintype "passive"))
    )
    (net (code "21") (name "Net-(IC1B-VDD12_RXBUF)") (class "Default")
      (node (ref "C73") (pin "1") (pinfunction "1_1") (pintype "passive"))
      (node (ref "FR29") (pin "1") (pinfunction "1_1") (pintype "passive"))
      (node (ref "IC1") (pin "AP26") (pinfunction "VDD12_RXBUF_AP26") (pintype "passive"))
    )
    (net (code "22") (name "Net-(IC1B-VDD12_TIA_RFE)") (class "Default")
      (node (ref "C67") (pin "1") (pinfunction "1_1") (pintype "passive"))
      (node (ref "FR27") (pin "2") (pinfunction "2_2") (pintype "passive"))
      (node (ref "IC1") (pin "AD6") (pinfunction "VDD12_TIA_RFE_AD6") (pintype "passive"))
    )
    (net (code "23") (name "Net-(IC1B-VDD12_TXBUF)") (class "Default")
      (node (ref "C61") (pin "1") (pinfunction "1_1") (pintype "passive"))
      (node (ref "FR20") (pin "2") (pinfunction "2_2") (pintype "passive"))
      (node (ref "IC1") (pin "G5") (pinfunction "VDD12_TXBUF_G5") (pintype "passive"))
    )
    (net (code "24") (name "Net-(IC1B-VDD12_VCO_SXR)") (class "Default")
      (node (ref "C60") (pin "1") (pinfunction "1_1") (pintype "passive"))
      (node (ref "FR15") (pin "1") (pinfunction "1_1") (pintype "passive"))
      (node (ref "IC1") (pin "AN23") (pinfunction "VDD12_VCO_SXR_AN23") (pintype "passive"))
    )
    (net (code "25") (name "Net-(IC1B-VDD12_VCO_SXT)") (class "Default")
      (node (ref "C58") (pin "2") (pinfunction "2_2") (pintype "passive"))
      (node (ref "FR14") (pin "2") (pinfunction "2_2") (pintype "passive"))
      (node (ref "IC1") (pin "K6") (pinfunction "VDD12_VCO_SXT_K6") (pintype "passive"))
      (node (ref "R28") (pin "2") (pinfunction "2_2") (pintype "passive"))
    )
    (net (code "26") (name "Net-(IC1B-VDD14_LNA_RFE)") (class "Default")
      (node (ref "C78") (pin "1") (pinfunction "1_1") (pintype "passive"))
      (node (ref "FR33") (pin "1") (pinfunction "1_1") (pintype "passive"))
      (node (ref "IC1") (pin "AF6") (pinfunction "VDD14_LNA_RFE_AF6") (pintype "passive"))
    )
    (net (code "27") (name "Net-(IC1B-VDD14_RBB)") (class "Default")
      (node (ref "C79") (pin "1") (pinfunction "1_1") (pintype "passive"))
      (node (ref "FR34") (pin "1") (pinfunction "1_1") (pintype "passive"))
      (node (ref "IC1") (pin "AD4") (pinfunction "VDD14_RBB_AD4") (pintype "passive"))
    )
    (net (code "28") (name "Net-(IC1B-VDD14_TIA_RFE)") (class "Default")
      (node (ref "C80") (pin "1") (pinfunction "1_1") (pintype "passive"))
      (node (ref "FR35") (pin "1") (pinfunction "1_1") (pintype "passive"))
      (node (ref "IC1") (pin "AF2") (pinfunction "VDD14_TIA_RFE_AF2") (pintype "passive"))
    )
    (net (code "29") (name "Net-(IC1B-VDD14_VCO_CGEN)") (class "Default")
      (node (ref "C56") (pin "1") (pinfunction "1_1") (pintype "passive"))
      (node (ref "FR17") (pin "1") (pinfunction "1_1") (pintype "passive"))
      (node (ref "IC1") (pin "C21") (pinfunction "VDD14_VCO_CGEN_C21") (pintype "passive"))
    )
    (net (code "30") (name "Net-(IC1B-VDD18_BIAS)") (class "Default")
      (node (ref "C46") (pin "1") (pinfunction "1_1") (pintype "passive"))
      (node (ref "FR3") (pin "1") (pinfunction "1_1") (pintype "passive"))
      (node (ref "IC1") (pin "E17") (pinfunction "VDD18_BIAS_E17") (pintype "passive"))
    )
    (net (code "31") (name "Net-(IC1B-VDD18_DIG)") (class "Default")
      (node (ref "C41") (pin "1") (pinfunction "1_1") (pintype "passive"))
      (node (ref "IC1") (pin "D24") (pinfunction "VDD18_DIG_D24") (pintype "passive"))
      (node (ref "R25") (pin "1") (pinfunction "1_1") (pintype "passive"))
    )
    (net (code "32") (name "Net-(IC1B-VDD18_LDO_RX)") (class "Default")
      (node (ref "C68") (pin "1") (pinfunction "1_1") (pintype "passive"))
      (node (ref "FR23") (pin "2") (pinfunction "2_2") (pintype "passive"))
      (node (ref "IC1") (pin "AE3") (pinfunction "VDD18_TIA_RFE_AE3") (pintype "passive"))
      (node (ref "IC1") (pin "AF4") (pinfunction "VDD18_LDO_RX_AF4") (pintype "passive"))
    )
    (net (code "33") (name "Net-(IC1B-VDD18_LDO_TX)") (class "Default")
      (node (ref "C62") (pin "1") (pinfunction "1_1") (pintype "passive"))
      (node (ref "FR21") (pin "2") (pinfunction "2_2") (pintype "passive"))
      (node (ref "IC1") (pin "N1") (pinfunction "VDD18_LDO_TX_N1") (pintype "passive"))
    )
    (net (code "34") (name "Net-(IC1B-VDD18_RXBUF)") (class "Default")
      (node (ref "C75") (pin "1") (pinfunction "1_1") (pintype "passive"))
      (node (ref "FR31") (pin "1") (pinfunction "1_1") (pintype "passive"))
      (node (ref "IC1") (pin "AM26") (pinfunction "VDD18_RXBUF_AM26") (pintype "passive"))
    )
    (net (code "35") (name "Net-(IC1B-VDD18_SXR)") (class "Default")
      (node (ref "C63") (pin "1") (pinfunction "1_1") (pintype "passive"))
      (node (ref "FR19") (pin "1") (pinfunction "1_1") (pintype "passive"))
      (node (ref "IC1") (pin "AM18") (pinfunction "VDD18_SXR_AM18") (pintype "passive"))
    )
    (net (code "36") (name "Net-(IC1B-VDD18_TRF)") (class "Default")
      (node (ref "C45") (pin "1") (pinfunction "1_1") (pintype "passive"))
      (node (ref "FR6") (pin "1") (pinfunction "1_1") (pintype "passive"))
      (node (ref "IC1") (pin "D16") (pinfunction "VDD18_TRF_D16") (pintype "passive"))
    )
    (net (code "37") (name "Net-(IC1B-VDD18_TXBUF)") (class "Default")
      (node (ref "C50") (pin "1") (pinfunction "1_1") (pintype "passive"))
      (node (ref "FR10") (pin "2") (pinfunction "2_2") (pintype "passive"))
      (node (ref "IC1") (pin "H6") (pinfunction "VDD18_TXBUF_H6") (pintype "passive"))
    )
    (net (code "38") (name "Net-(IC1B-VDD18_VCO_CGEN)") (class "Default")
      (node (ref "C44") (pin "1") (pinfunction "1_1") (pintype "passive"))
      (node (ref "FR7") (pin "1") (pinfunction "1_1") (pintype "passive"))
      (node (ref "IC1") (pin "E21") (pinfunction "VDD18_VCO_CGEN_E21") (pintype "passive"))
    )
    (net (code "39") (name "Net-(IC1B-VDD18_VCO_SXR)") (class "Default")
      (node (ref "C77") (pin "1") (pinfunction "1_1") (pintype "passive"))
      (node (ref "FR32") (pin "1") (pinfunction "1_1") (pintype "passive"))
      (node (ref "IC1") (pin "AK22") (pinfunction "VDD18_VCO_SXR_AK22") (pintype "passive"))
    )
    (net (code "40") (name "Net-(IC1B-VDD18_VCO_SXT)") (class "Default")
      (node (ref "C48") (pin "1") (pinfunction "1_1") (pintype "passive"))
      (node (ref "FR12") (pin "1") (pinfunction "1_1") (pintype "passive"))
      (node (ref "IC1") (pin "G3") (pinfunction "VDD18_VCO_SXT_G3") (pintype "passive"))
    )
    (net (code "41") (name "Net-(IC1B-VDDO_DIV_SXT)") (class "Default")
      (node (ref "IC1") (pin "K2") (pinfunction "VDDO_DIV_SXT_K2") (pintype "passive"))
      (node (ref "R31") (pin "1") (pinfunction "1_1") (pintype "passive"))
    )
    (net (code "42") (name "Net-(IC1B-VDDO_TLOBUF_TRF)") (class "Default")
      (node (ref "IC1") (pin "D6") (pinfunction "VDDO_TLOBUF_TRF_D6") (pintype "passive"))
      (node (ref "R26") (pin "2") (pinfunction "2_2") (pintype "passive"))
    )
    (net (code "43") (name "Net-(IC1B-VDD_AFE)") (class "Default")
      (node (ref "C70") (pin "1") (pinfunction "1_1") (pintype "passive"))
      (node (ref "FR26") (pin "1") (pinfunction "1_1") (pintype "passive"))
      (node (ref "IC1") (pin "AJ25") (pinfunction "VDD_AFE_AJ25") (pintype "passive"))
    )
    (net (code "44") (name "Net-(IC1B-VDD_CP_CGEN)") (class "Default")
      (node (ref "C57") (pin "1") (pinfunction "1_1") (pintype "passive"))
      (node (ref "IC1") (pin "F20") (pinfunction "VDD_CP_CGEN_F20") (pintype "passive"))
      (node (ref "R29") (pin "2") (pinfunction "2_2") (pintype "passive"))
    )
    (net (code "45") (name "Net-(IC1B-VDD_CP_SXR)") (class "Default")
      (node (ref "C64") (pin "1") (pinfunction "1_1") (pintype "passive"))
      (node (ref "IC1") (pin "AL19") (pinfunction "VDD_CP_SXR_AL19") (pintype "passive"))
      (node (ref "R32") (pin "2") (pinfunction "2_2") (pintype "passive"))
    )
    (net (code "46") (name "Net-(IC1B-VDD_CP_SXT)") (class "Default")
      (node (ref "C55") (pin "1") (pinfunction "1_1") (pintype "passive"))
      (node (ref "IC1") (pin "J3") (pinfunction "VDD_CP_SXT_J3") (pintype "passive"))
      (node (ref "R30") (pin "1") (pinfunction "1_1") (pintype "passive"))
    )
    (net (code "47") (name "Net-(IC1B-VDD_DIV_CGEN)") (class "Default")
      (node (ref "C54") (pin "1") (pinfunction "1_1") (pintype "passive"))
      (node (ref "FR13") (pin "1") (pinfunction "1_1") (pintype "passive"))
      (node (ref "IC1") (pin "E19") (pinfunction "VDD_DIV_CGEN_E19") (pintype "passive"))
    )
    (net (code "48") (name "Net-(IC1B-VDD_DIV_SXR)") (class "Default")
      (node (ref "C66") (pin "1") (pinfunction "1_1") (pintype "passive"))
      (node (ref "FR22") (pin "1") (pinfunction "1_1") (pintype "passive"))
      (node (ref "IC1") (pin "AM20") (pinfunction "VDD_DIV_SXR_AM20") (pintype "passive"))
    )
    (net (code "49") (name "Net-(IC1B-VDD_DIV_SXT)") (class "Default")
      (node (ref "C59") (pin "1") (pinfunction "1_1") (pintype "passive"))
      (node (ref "FR16") (pin "2") (pinfunction "2_2") (pintype "passive"))
      (node (ref "FR18") (pin "2") (pinfunction "2_2") (pintype "passive"))
      (node (ref "IC1") (pin "L5") (pinfunction "VDD_DIV_SXT_L5") (pintype "passive"))
      (node (ref "R31") (pin "2") (pinfunction "2_2") (pintype "passive"))
    )
    (net (code "50") (name "Net-(IC1B-VDD_MXLOBUF_RFE)") (class "Default")
      (node (ref "C69") (pin "1") (pinfunction "1_1") (pintype "passive"))
      (node (ref "FR24") (pin "1") (pinfunction "1_1") (pintype "passive"))
      (node (ref "FR25") (pin "1") (pinfunction "1_1") (pintype "passive"))
      (node (ref "IC1") (pin "AN17") (pinfunction "VDD_MXLOBUF_RFE_AN17") (pintype "passive"))
    )
    (net (code "51") (name "Net-(IC1B-VDD_SPI_BUF)") (class "Default")
      (node (ref "C43") (pin "1") (pinfunction "1_1") (pintype "passive"))
      (node (ref "FR4") (pin "2") (pinfunction "2_2") (pintype "passive"))
      (node (ref "IC1") (pin "F24") (pinfunction "VDD_SPI_BUF_F24") (pintype "passive"))
    )
    (net (code "52") (name "Net-(IC1B-VDD_TBB)") (class "Default")
      (node (ref "C72") (pin "1") (pinfunction "1_1") (pintype "passive"))
      (node (ref "FR30") (pin "2") (pinfunction "2_2") (pintype "passive"))
      (node (ref "IC1") (pin "P4") (pinfunction "VDD_TBB_P4") (pintype "passive"))
    )
    (net (code "53") (name "Net-(IC1B-VDD_TLOBUF_TRF)") (class "Default")
      (node (ref "C42") (pin "1") (pinfunction "1_1") (pintype "passive"))
      (node (ref "FR1") (pin "1") (pinfunction "1_1") (pintype "passive"))
      (node (ref "IC1") (pin "F8") (pinfunction "VDD_TLOBUF_TRF_F8") (pintype "passive"))
      (node (ref "R26") (pin "1") (pinfunction "1_1") (pintype "passive"))
    )
    (net (code "54") (name "Net-(IC1B-VDD_TPAD_TRF)") (class "Default")
      (node (ref "C51") (pin "1") (pinfunction "1_1") (pintype "passive"))
      (node (ref "FR8") (pin "1") (pinfunction "1_1") (pintype "passive"))
      (node (ref "IC1") (pin "B16") (pinfunction "VDD_TPAD_TRF_B16") (pintype "passive"))
    )
    (net (code "55") (name "VCC1P4_LMS") (class "Default")
      (node (ref "FR16") (pin "1") (pinfunction "1_1") (pintype "passive"))
      (node (ref "FR17") (pin "2") (pinfunction "2_2") (pintype "passive"))
      (node (ref "FR24") (pin "2") (pinfunction "2_2") (pintype "passive"))
      (node (ref "FR33") (pin "2") (pinfunction "2_2") (pintype "passive"))
      (node (ref "FR34") (pin "2") (pinfunction "2_2") (pintype "passive"))
      (node (ref "FR35") (pin "2") (pinfunction "2_2") (pintype "passive"))
    )
    (net (code "56") (name "VCC1P8_LMS") (class "Default")
      (node (ref "FR12") (pin "2") (pinfunction "2_2") (pintype "passive"))
      (node (ref "FR19") (pin "2") (pinfunction "2_2") (pintype "passive"))
      (node (ref "FR21") (pin "1") (pinfunction "1_1") (pintype "passive"))
      (node (ref "FR23") (pin "1") (pinfunction "1_1") (pintype "passive"))
      (node (ref "FR3") (pin "2") (pinfunction "2_2") (pintype "passive"))
      (node (ref "FR32") (pin "2") (pinfunction "2_2") (pintype "passive"))
      (node (ref "FR6") (pin "2") (pinfunction "2_2") (pintype "passive"))
      (node (ref "FR7") (pin "2") (pinfunction "2_2") (pintype "passive"))
      (node (ref "R25") (pin "2") (pinfunction "2_2") (pintype "passive"))
      (node (ref "R27") (pin "2") (pinfunction "2_2") (pintype "passive"))
      (node (ref "R35") (pin "1") (pinfunction "1_1") (pintype "passive"))
    )
    (net (code "57") (name "VCC1P25_LMS") (class "Default")
      (node (ref "FR1") (pin "2") (pinfunction "2_2") (pintype "passive"))
      (node (ref "FR11") (pin "2") (pinfunction "2_2") (pintype "passive"))
      (node (ref "FR13") (pin "2") (pinfunction "2_2") (pintype "passive"))
      (node (ref "FR14") (pin "1") (pinfunction "1_1") (pintype "passive"))
      (node (ref "FR15") (pin "2") (pinfunction "2_2") (pintype "passive"))
      (node (ref "FR18") (pin "1") (pinfunction "1_1") (pintype "passive"))
      (node (ref "FR2") (pin "1") (pinfunction "1_1") (pintype "passive"))
      (node (ref "FR22") (pin "2") (pinfunction "2_2") (pintype "passive"))
      (node (ref "FR25") (pin "2") (pinfunction "2_2") (pintype "passive"))
      (node (ref "FR26") (pin "2") (pinfunction "2_2") (pintype "passive"))
      (node (ref "FR27") (pin "1") (pinfunction "1_1") (pintype "passive"))
      (node (ref "FR28") (pin "1") (pinfunction "1_1") (pintype "passive"))
      (node (ref "FR30") (pin "1") (pinfunction "1_1") (pintype "passive"))
      (node (ref "FR4") (pin "1") (pinfunction "1_1") (pintype "passive"))
      (node (ref "FR5") (pin "1") (pinfunction "1_1") (pintype "passive"))
      (node (ref "FR8") (pin "2") (pinfunction "2_2") (pintype "passive"))
      (node (ref "FR9") (pin "1") (pinfunction "1_1") (pintype "passive"))
      (node (ref "R29") (pin "1") (pinfunction "1_1") (pintype "passive"))
      (node (ref "R30") (pin "2") (pinfunction "2_2") (pintype "passive"))
      (node (ref "R32") (pin "1") (pinfunction "1_1") (pintype "passive"))
      (node (ref "R33") (pin "2") (pinfunction "2_2") (pintype "passive"))
      (node (ref "R34") (pin "1") (pinfunction "1_1") (pintype "passive"))
    )
    (net (code "58") (name "VCC1P25_LMS_DIG") (class "Default")
      (node (ref "R16") (pin "2") (pinfunction "2_2") (pintype "passive"))
      (node (ref "R18") (pin "2") (pinfunction "2_2") (pintype "passive"))
      (node (ref "R20") (pin "2") (pinfunction "2_2") (pintype "passive"))
      (node (ref "R22") (pin "2") (pinfunction "2_2") (pintype "passive"))
    )
    (net (code "59") (name "VDIO_LMS") (class "Default")
      (node (ref "R17") (pin "1") (pinfunction "1_1") (pintype "passive"))
      (node (ref "R19") (pin "1") (pinfunction "1_1") (pintype "passive"))
      (node (ref "R21") (pin "1") (pinfunction "1_1") (pintype "passive"))
      (node (ref "R23") (pin "1") (pinfunction "1_1") (pintype "passive"))
      (node (ref "R24") (pin "1") (pinfunction "1_1") (pintype "passive"))
    )
  )
)
